# First_schematic.net
KiCad netlist of a schematic drawn in EAGLE
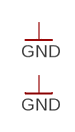
[diagram p0: schematic, sheet 1, part 1 of 2]
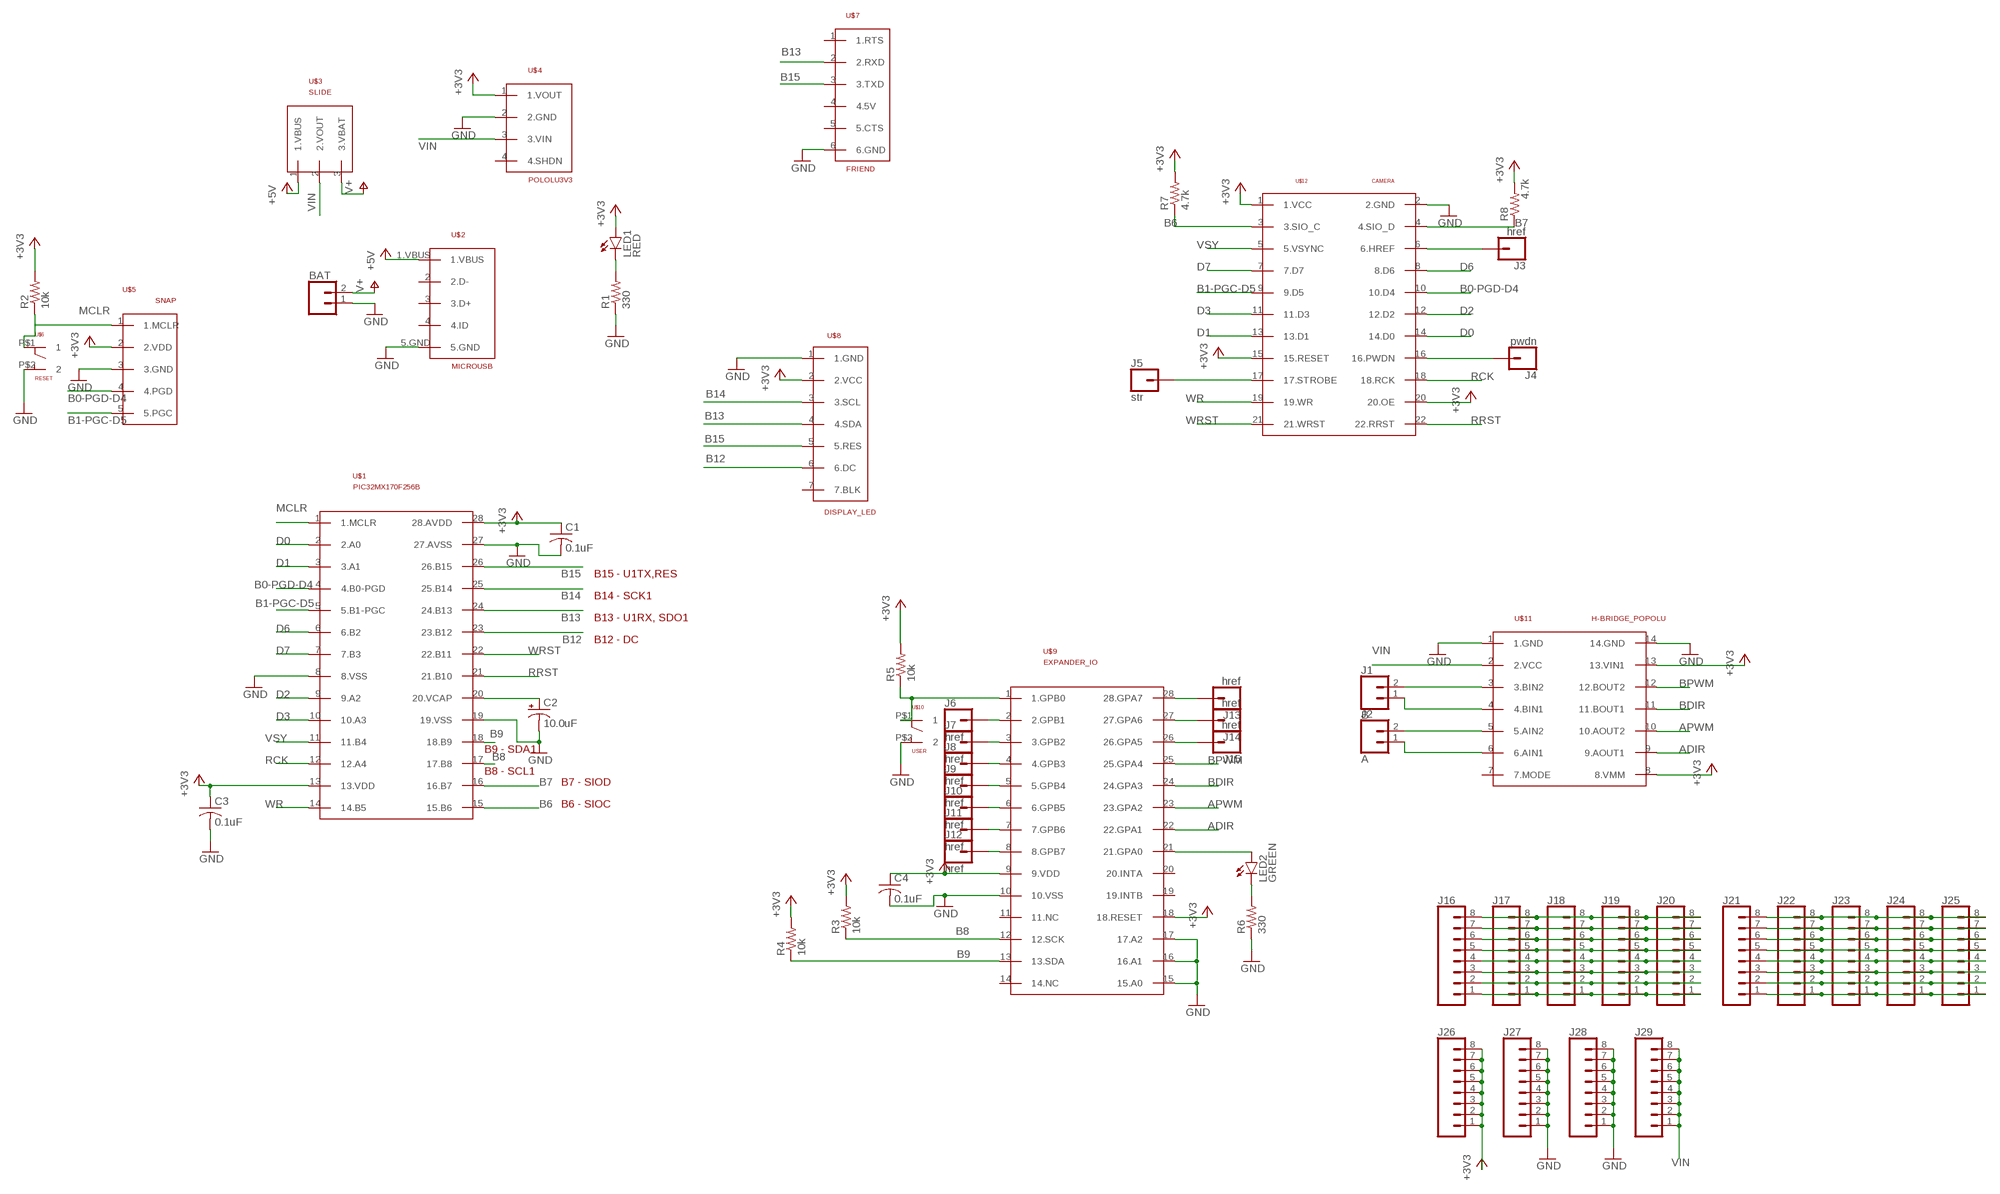
[diagram p1: schematic, sheet 1, part 2 of 2]

(export (version "E")
  (design (tool "Eeschema 10.0.6"))
  (components
    (comp (ref "BAT")
      (value "CONN_02")
      (footprint "eagle-import:1X02")
      (libsource (lib "eagle-import") (part "CONN_02"))
    )
    (comp (ref "C1")
      (value "0.1uF")
      (footprint "eagle-import:C025-030X050")
      (libsource (lib "eagle-import") (part "C-US025-030X050"))
    )
    (comp (ref "C2")
      (value "10.0uF")
      (footprint "eagle-import:B45181B")
      (libsource (lib "eagle-import") (part "CPOL-USB45181B"))
    )
    (comp (ref "C3")
      (value "0.1uF")
      (footprint "eagle-import:C025-030X050")
      (libsource (lib "eagle-import") (part "C-US025-030X050"))
    )
    (comp (ref "C4")
      (value "0.1uF")
      (footprint "eagle-import:C025-030X050")
      (libsource (lib "eagle-import") (part "C-US025-030X050"))
    )
    (comp (ref "J1")
      (value "B")
      (footprint "eagle-import:1X02")
      (libsource (lib "eagle-import") (part "CONN_02"))
    )
    (comp (ref "J2")
      (value "A")
      (footprint "eagle-import:1X02")
      (libsource (lib "eagle-import") (part "CONN_02"))
    )
    (comp (ref "J3")
      (value "href")
      (footprint "eagle-import:1X01")
      (libsource (lib "eagle-import") (part "CONN_01"))
    )
    (comp (ref "J4")
      (value "pwdn")
      (footprint "eagle-import:1X01")
      (libsource (lib "eagle-import") (part "CONN_01"))
    )
    (comp (ref "J5")
      (value "str")
      (footprint "eagle-import:1X01")
      (libsource (lib "eagle-import") (part "CONN_01"))
    )
    (comp (ref "J6")
      (value "href")
      (footprint "eagle-import:1X01")
      (libsource (lib "eagle-import") (part "CONN_01"))
    )
    (comp (ref "J7")
      (value "href")
      (footprint "eagle-import:1X01")
      (libsource (lib "eagle-import") (part "CONN_01"))
    )
    (comp (ref "J8")
      (value "href")
      (footprint "eagle-import:1X01")
      (libsource (lib "eagle-import") (part "CONN_01"))
    )
    (comp (ref "J9")
      (value "href")
      (footprint "eagle-import:1X01")
      (libsource (lib "eagle-import") (part "CONN_01"))
    )
    (comp (ref "J10")
      (value "href")
      (footprint "eagle-import:1X01")
      (libsource (lib "eagle-import") (part "CONN_01"))
    )
    (comp (ref "J11")
      (value "href")
      (footprint "eagle-import:1X01")
      (libsource (lib "eagle-import") (part "CONN_01"))
    )
    (comp (ref "J12")
      (value "href")
      (footprint "eagle-import:1X01")
      (libsource (lib "eagle-import") (part "CONN_01"))
    )
    (comp (ref "J13")
      (value "href")
      (footprint "eagle-import:1X01")
      (libsource (lib "eagle-import") (part "CONN_01"))
    )
    (comp (ref "J14")
      (value "href")
      (footprint "eagle-import:1X01")
      (libsource (lib "eagle-import") (part "CONN_01"))
    )
    (comp (ref "J15")
      (value "href")
      (footprint "eagle-import:1X01")
      (libsource (lib "eagle-import") (part "CONN_01"))
    )
    (comp (ref "J16")
      (value "CONN_08\"")
      (footprint "eagle-import:1X08")
      (libsource (lib "eagle-import") (part "CONN_08{dblquote}"))
    )
    (comp (ref "J17")
      (value "CONN_08\"")
      (footprint "eagle-import:1X08")
      (libsource (lib "eagle-import") (part "CONN_08{dblquote}"))
    )
    (comp (ref "J18")
      (value "CONN_08\"")
      (footprint "eagle-import:1X08")
      (libsource (lib "eagle-import") (part "CONN_08{dblquote}"))
    )
    (comp (ref "J19")
      (value "CONN_08\"")
      (footprint "eagle-import:1X08")
      (libsource (lib "eagle-import") (part "CONN_08{dblquote}"))
    )
    (comp (ref "J20")
      (value "CONN_08\"")
      (footprint "eagle-import:1X08")
      (libsource (lib "eagle-import") (part "CONN_08{dblquote}"))
    )
    (comp (ref "J21")
      (value "CONN_08\"")
      (footprint "eagle-import:1X08")
      (libsource (lib "eagle-import") (part "CONN_08{dblquote}"))
    )
    (comp (ref "J22")
      (value "CONN_08\"")
      (footprint "eagle-import:1X08")
      (libsource (lib "eagle-import") (part "CONN_08{dblquote}"))
    )
    (comp (ref "J23")
      (value "CONN_08\"")
      (footprint "eagle-import:1X08")
      (libsource (lib "eagle-import") (part "CONN_08{dblquote}"))
    )
    (comp (ref "J24")
      (value "CONN_08\"")
      (footprint "eagle-import:1X08")
      (libsource (lib "eagle-import") (part "CONN_08{dblquote}"))
    )
    (comp (ref "J25")
      (value "CONN_08\"")
      (footprint "eagle-import:1X08")
      (libsource (lib "eagle-import") (part "CONN_08{dblquote}"))
    )
    (comp (ref "J26")
      (value "CONN_08\"")
      (footprint "eagle-import:1X08")
      (libsource (lib "eagle-import") (part "CONN_08{dblquote}"))
    )
    (comp (ref "J27")
      (value "CONN_08\"")
      (footprint "eagle-import:1X08")
      (libsource (lib "eagle-import") (part "CONN_08{dblquote}"))
    )
    (comp (ref "J28")
      (value "CONN_08\"")
      (footprint "eagle-import:1X08")
      (libsource (lib "eagle-import") (part "CONN_08{dblquote}"))
    )
    (comp (ref "J29")
      (value "CONN_08\"")
      (footprint "eagle-import:1X08")
      (libsource (lib "eagle-import") (part "CONN_08{dblquote}"))
    )
    (comp (ref "LED1")
      (value "RED")
      (footprint "eagle-import:LED3MM")
      (libsource (lib "eagle-import") (part "LED3MM"))
    )
    (comp (ref "LED2")
      (value "GREEN")
      (footprint "eagle-import:LED3MM")
      (libsource (lib "eagle-import") (part "LED3MM"))
    )
    (comp (ref "R1")
      (value "330")
      (footprint "eagle-import:0207_10")
      (libsource (lib "eagle-import") (part "R-US_0207/10"))
    )
    (comp (ref "R2")
      (value "10k")
      (footprint "eagle-import:0207_10")
      (libsource (lib "eagle-import") (part "R-US_0207/10"))
    )
    (comp (ref "R3")
      (value "10k")
      (footprint "eagle-import:0207_10")
      (libsource (lib "eagle-import") (part "R-US_0207/10"))
    )
    (comp (ref "R4")
      (value "10k")
      (footprint "eagle-import:0207_10")
      (libsource (lib "eagle-import") (part "R-US_0207/10"))
    )
    (comp (ref "R5")
      (value "10k")
      (footprint "eagle-import:0207_10")
      (libsource (lib "eagle-import") (part "R-US_0207/10"))
    )
    (comp (ref "R6")
      (value "330")
      (footprint "eagle-import:0207_10")
      (libsource (lib "eagle-import") (part "R-US_0207/10"))
    )
    (comp (ref "R7")
      (value "4.7k")
      (footprint "eagle-import:0207_10")
      (libsource (lib "eagle-import") (part "R-US_0207/10"))
    )
    (comp (ref "R8")
      (value "4.7k")
      (footprint "eagle-import:0207_10")
      (libsource (lib "eagle-import") (part "R-US_0207/10"))
    )
    (comp (ref "U$1")
      (value "PIC32MX170F256B")
      (footprint "eagle-import:DIL28-3")
      (libsource (lib "eagle-import") (part "PIC32MX170F256B"))
    )
    (comp (ref "U$2")
      (value "MICROUSB")
      (footprint "eagle-import:MICROUSB")
      (libsource (lib "eagle-import") (part "MICROUSB"))
    )
    (comp (ref "U$3")
      (value "SLIDE")
      (footprint "eagle-import:SLIDE")
      (libsource (lib "eagle-import") (part "SLIDE"))
    )
    (comp (ref "U$4")
      (value "POLOLU3V3")
      (footprint "eagle-import:POLOLU3V3")
      (libsource (lib "eagle-import") (part "POLOLU3V3"))
    )
    (comp (ref "U$5")
      (value "SNAP")
      (footprint "eagle-import:1X05")
      (libsource (lib "eagle-import") (part "SNAP"))
    )
    (comp (ref "U$6")
      (value "RESET")
      (footprint "eagle-import:PUSH")
      (libsource (lib "eagle-import") (part "PUSH"))
    )
    (comp (ref "U$7")
      (value "FRIEND")
      (footprint "eagle-import:FRIEND")
      (libsource (lib "eagle-import") (part "FRIEND"))
    )
    (comp (ref "U$8")
      (value "DISPLAY_LED")
      (footprint "eagle-import:DISPLAY_LED")
      (libsource (lib "eagle-import") (part "DISPLAY_LED"))
    )
    (comp (ref "U$9")
      (value "EXPANDER_IO")
      (footprint "eagle-import:DIL28-3")
      (libsource (lib "eagle-import") (part "EXPANDER_IO"))
    )
    (comp (ref "U$10")
      (value "USER")
      (footprint "eagle-import:PUSH")
      (libsource (lib "eagle-import") (part "PUSH"))
    )
    (comp (ref "U$11")
      (value "H-BRIDGE_POPOLU")
      (footprint "eagle-import:H-BRIDGE_POLOLU")
      (libsource (lib "eagle-import") (part "H-BRIDGE_POPOLU"))
    )
    (comp (ref "U$12")
      (value "CAMERA")
      (footprint "eagle-import:CAMERA_REAL_SIZE")
      (libsource (lib "eagle-import") (part "CAMERA"))
    )
  )
  (nets
    (net (code "1") (name "+3V3") (class "Default")
      (node (ref "C1") (pin "1") (pinfunction "1_1") (pintype "passive"))
      (node (ref "C3") (pin "1") (pinfunction "1_1") (pintype "passive"))
      (node (ref "C4") (pin "1") (pinfunction "1_1") (pintype "passive"))
      (node (ref "J26") (pin "1") (pinfunction "1_1") (pintype "passive"))
      (node (ref "J26") (pin "2") (pinfunction "2_2") (pintype "passive"))
      (node (ref "J26") (pin "3") (pinfunction "3_3") (pintype "passive"))
      (node (ref "J26") (pin "4") (pinfunction "4_4") (pintype "passive"))
      (node (ref "J26") (pin "5") (pinfunction "5_5") (pintype "passive"))
      (node (ref "J26") (pin "6") (pinfunction "6_6") (pintype "passive"))
      (node (ref "J26") (pin "7") (pinfunction "7_7") (pintype "passive"))
      (node (ref "J26") (pin "8") (pinfunction "8_8") (pintype "passive"))
      (node (ref "LED1") (pin "A") (pinfunction "A_A") (pintype "passive"))
      (node (ref "R2") (pin "2") (pinfunction "2_2") (pintype "passive"))
      (node (ref "R3") (pin "2") (pinfunction "2_2") (pintype "passive"))
      (node (ref "R4") (pin "2") (pinfunction "2_2") (pintype "passive"))
      (node (ref "R5") (pin "2") (pinfunction "2_2") (pintype "passive"))
      (node (ref "R7") (pin "2") (pinfunction "2_2") (pintype "passive"))
      (node (ref "R8") (pin "2") (pinfunction "2_2") (pintype "passive"))
      (node (ref "U$1") (pin "13") (pinfunction "13.VDD_13") (pintype "bidirectional"))
      (node (ref "U$1") (pin "28") (pinfunction "28.AVDD_28") (pintype "bidirectional"))
      (node (ref "U$11") (pin "13") (pinfunction "13.VIN1_13") (pintype "bidirectional"))
      (node (ref "U$11") (pin "8") (pinfunction "8.VMM_8") (pintype "bidirectional"))
      (node (ref "U$12") (pin "1") (pinfunction "1.VCC_1") (pintype "bidirectional"))
      (node (ref "U$12") (pin "15") (pinfunction "15.RESET_15") (pintype "bidirectional"))
      (node (ref "U$12") (pin "20") (pinfunction "20.OE_20") (pintype "bidirectional"))
      (node (ref "U$4") (pin "1") (pinfunction "1.VOUT_1") (pintype "bidirectional"))
      (node (ref "U$5") (pin "2") (pinfunction "2.VDD_2") (pintype "bidirectional"))
      (node (ref "U$8") (pin "2") (pinfunction "2.VCC_2") (pintype "bidirectional"))
      (node (ref "U$9") (pin "18") (pinfunction "18.RESET_18") (pintype "bidirectional"))
      (node (ref "U$9") (pin "9") (pinfunction "9.VDD_9") (pintype "bidirectional"))
    )
    (net (code "2") (name "+5V") (class "Default")
      (node (ref "U$2") (pin "1.VBUS") (pinfunction "1.VBUS_1.VBUS") (pintype "bidirectional"))
      (node (ref "U$3") (pin "1") (pinfunction "1.VBUS_1") (pintype "bidirectional"))
    )
    (net (code "3") (name "/ADIR") (class "Default")
      (node (ref "U$11") (pin "9") (pinfunction "9.AOUT1_9") (pintype "bidirectional"))
      (node (ref "U$9") (pin "22") (pinfunction "22.GPA1_22") (pintype "bidirectional"))
    )
    (net (code "4") (name "/APWM") (class "Default")
      (node (ref "U$11") (pin "10") (pinfunction "10.AOUT2_10") (pintype "bidirectional"))
      (node (ref "U$9") (pin "23") (pinfunction "23.GPA2_23") (pintype "bidirectional"))
    )
    (net (code "5") (name "/B0-PGD-D4") (class "Default")
      (node (ref "U$1") (pin "4") (pinfunction "4.B0-PGD_4") (pintype "bidirectional"))
      (node (ref "U$12") (pin "10") (pinfunction "10.D4_10") (pintype "bidirectional"))
      (node (ref "U$5") (pin "4") (pinfunction "4.PGD_4") (pintype "bidirectional"))
    )
    (net (code "6") (name "/B1-PGC-D5") (class "Default")
      (node (ref "U$1") (pin "5") (pinfunction "5.B1-PGC_5") (pintype "bidirectional"))
      (node (ref "U$12") (pin "9") (pinfunction "9.D5_9") (pintype "bidirectional"))
      (node (ref "U$5") (pin "5") (pinfunction "5.PGC_5") (pintype "bidirectional"))
    )
    (net (code "7") (name "/B6") (class "Default")
      (node (ref "R7") (pin "1") (pinfunction "1_1") (pintype "passive"))
      (node (ref "U$1") (pin "15") (pinfunction "15.B6_15") (pintype "bidirectional"))
      (node (ref "U$12") (pin "3") (pinfunction "3.SIO_C_3") (pintype "bidirectional"))
    )
    (net (code "8") (name "/B7") (class "Default")
      (node (ref "R8") (pin "1") (pinfunction "1_1") (pintype "passive"))
      (node (ref "U$1") (pin "16") (pinfunction "16.B7_16") (pintype "bidirectional"))
      (node (ref "U$12") (pin "4") (pinfunction "4.SIO_D_4") (pintype "bidirectional"))
    )
    (net (code "9") (name "/B8") (class "Default")
      (node (ref "R3") (pin "1") (pinfunction "1_1") (pintype "passive"))
      (node (ref "U$1") (pin "17") (pinfunction "17.B8_17") (pintype "bidirectional"))
      (node (ref "U$9") (pin "12") (pinfunction "12.SCK_12") (pintype "bidirectional"))
    )
    (net (code "10") (name "/B9") (class "Default")
      (node (ref "R4") (pin "1") (pinfunction "1_1") (pintype "passive"))
      (node (ref "U$1") (pin "18") (pinfunction "18.B9_18") (pintype "bidirectional"))
      (node (ref "U$9") (pin "13") (pinfunction "13.SDA_13") (pintype "bidirectional"))
    )
    (net (code "11") (name "/B12") (class "Default")
      (node (ref "U$1") (pin "23") (pinfunction "23.B12_23") (pintype "bidirectional"))
      (node (ref "U$8") (pin "6") (pinfunction "6.DC_6") (pintype "bidirectional"))
    )
    (net (code "12") (name "/B13") (class "Default")
      (node (ref "U$1") (pin "24") (pinfunction "24.B13_24") (pintype "bidirectional"))
      (node (ref "U$7") (pin "2") (pinfunction "2.RXD_2") (pintype "bidirectional"))
      (node (ref "U$8") (pin "4") (pinfunction "4.SDA_4") (pintype "bidirectional"))
    )
    (net (code "13") (name "/B14") (class "Default")
      (node (ref "U$1") (pin "25") (pinfunction "25.B14_25") (pintype "bidirectional"))
      (node (ref "U$8") (pin "3") (pinfunction "3.SCL_3") (pintype "bidirectional"))
    )
    (net (code "14") (name "/B15") (class "Default")
      (node (ref "U$1") (pin "26") (pinfunction "26.B15_26") (pintype "bidirectional"))
      (node (ref "U$7") (pin "3") (pinfunction "3.TXD_3") (pintype "bidirectional"))
      (node (ref "U$8") (pin "5") (pinfunction "5.RES_5") (pintype "bidirectional"))
    )
    (net (code "15") (name "/BDIR") (class "Default")
      (node (ref "U$11") (pin "11") (pinfunction "11.BOUT1_11") (pintype "bidirectional"))
      (node (ref "U$9") (pin "24") (pinfunction "24.GPA3_24") (pintype "bidirectional"))
    )
    (net (code "16") (name "/BPWM") (class "Default")
      (node (ref "U$11") (pin "12") (pinfunction "12.BOUT2_12") (pintype "bidirectional"))
      (node (ref "U$9") (pin "25") (pinfunction "25.GPA4_25") (pintype "bidirectional"))
    )
    (net (code "17") (name "/D0") (class "Default")
      (node (ref "U$1") (pin "2") (pinfunction "2.A0_2") (pintype "bidirectional"))
      (node (ref "U$12") (pin "14") (pinfunction "14.D0_14") (pintype "bidirectional"))
    )
    (net (code "18") (name "/D1") (class "Default")
      (node (ref "U$1") (pin "3") (pinfunction "3.A1_3") (pintype "bidirectional"))
      (node (ref "U$12") (pin "13") (pinfunction "13.D1_13") (pintype "bidirectional"))
    )
    (net (code "19") (name "/D2") (class "Default")
      (node (ref "U$1") (pin "9") (pinfunction "9.A2_9") (pintype "bidirectional"))
      (node (ref "U$12") (pin "12") (pinfunction "12.D2_12") (pintype "bidirectional"))
    )
    (net (code "20") (name "/D3") (class "Default")
      (node (ref "U$1") (pin "10") (pinfunction "10.A3_10") (pintype "bidirectional"))
      (node (ref "U$12") (pin "11") (pinfunction "11.D3_11") (pintype "bidirectional"))
    )
    (net (code "21") (name "/D6") (class "Default")
      (node (ref "U$1") (pin "6") (pinfunction "6.B2_6") (pintype "bidirectional"))
      (node (ref "U$12") (pin "8") (pinfunction "8.D6_8") (pintype "bidirectional"))
    )
    (net (code "22") (name "/D7") (class "Default")
      (node (ref "U$1") (pin "7") (pinfunction "7.B3_7") (pintype "bidirectional"))
      (node (ref "U$12") (pin "7") (pinfunction "7.D7_7") (pintype "bidirectional"))
    )
    (net (code "23") (name "/MCLR") (class "Default")
      (node (ref "U$1") (pin "1") (pinfunction "1.MCLR_1") (pintype "bidirectional"))
      (node (ref "U$5") (pin "1") (pinfunction "1.MCLR_1") (pintype "bidirectional"))
    )
    (net (code "24") (name "/RCK") (class "Default")
      (node (ref "U$1") (pin "12") (pinfunction "12.A4_12") (pintype "bidirectional"))
      (node (ref "U$12") (pin "18") (pinfunction "18.RCK_18") (pintype "bidirectional"))
    )
    (net (code "25") (name "/RRST") (class "Default")
      (node (ref "U$1") (pin "21") (pinfunction "21.B10_21") (pintype "bidirectional"))
      (node (ref "U$12") (pin "22") (pinfunction "22.RRST_22") (pintype "bidirectional"))
    )
    (net (code "26") (name "/VIN") (class "Default")
      (node (ref "J29") (pin "1") (pinfunction "1_1") (pintype "passive"))
      (node (ref "J29") (pin "2") (pinfunction "2_2") (pintype "passive"))
      (node (ref "J29") (pin "3") (pinfunction "3_3") (pintype "passive"))
      (node (ref "J29") (pin "4") (pinfunction "4_4") (pintype "passive"))
      (node (ref "J29") (pin "5") (pinfunction "5_5") (pintype "passive"))
      (node (ref "J29") (pin "6") (pinfunction "6_6") (pintype "passive"))
      (node (ref "J29") (pin "7") (pinfunction "7_7") (pintype "passive"))
      (node (ref "J29") (pin "8") (pinfunction "8_8") (pintype "passive"))
      (node (ref "U$11") (pin "2") (pinfunction "2.VCC_2") (pintype "bidirectional"))
      (node (ref "U$3") (pin "2") (pinfunction "2.VOUT_2") (pintype "bidirectional"))
      (node (ref "U$4") (pin "3") (pinfunction "3.VIN_3") (pintype "bidirectional"))
    )
    (net (code "27") (name "/VSY") (class "Default")
      (node (ref "U$1") (pin "11") (pinfunction "11.B4_11") (pintype "bidirectional"))
      (node (ref "U$12") (pin "5") (pinfunction "5.VSYNC_5") (pintype "bidirectional"))
    )
    (net (code "28") (name "/WR") (class "Default")
      (node (ref "U$1") (pin "14") (pinfunction "14.B5_14") (pintype "bidirectional"))
      (node (ref "U$12") (pin "19") (pinfunction "19.WR_19") (pintype "bidirectional"))
    )
    (net (code "29") (name "/WRST") (class "Default")
      (node (ref "U$1") (pin "22") (pinfunction "22.B11_22") (pintype "bidirectional"))
      (node (ref "U$12") (pin "21") (pinfunction "21.WRST_21") (pintype "bidirectional"))
    )
    (net (code "30") (name "GND") (class "Default")
      (node (ref "BAT") (pin "1") (pinfunction "1_1") (pintype "passive"))
      (node (ref "C1") (pin "2") (pinfunction "2_2") (pintype "passive"))
      (node (ref "C2") (pin "-") (pinfunction "-_-") (pintype "passive"))
      (node (ref "C3") (pin "2") (pinfunction "2_2") (pintype "passive"))
      (node (ref "C4") (pin "2") (pinfunction "2_2") (pintype "passive"))
      (node (ref "J27") (pin "1") (pinfunction "1_1") (pintype "passive"))
      (node (ref "J27") (pin "2") (pinfunction "2_2") (pintype "passive"))
      (node (ref "J27") (pin "3") (pinfunction "3_3") (pintype "passive"))
      (node (ref "J27") (pin "4") (pinfunction "4_4") (pintype "passive"))
      (node (ref "J27") (pin "5") (pinfunction "5_5") (pintype "passive"))
      (node (ref "J27") (pin "6") (pinfunction "6_6") (pintype "passive"))
      (node (ref "J27") (pin "7") (pinfunction "7_7") (pintype "passive"))
      (node (ref "J27") (pin "8") (pinfunction "8_8") (pintype "passive"))
      (node (ref "J28") (pin "1") (pinfunction "1_1") (pintype "passive"))
      (node (ref "J28") (pin "2") (pinfunction "2_2") (pintype "passive"))
      (node (ref "J28") (pin "3") (pinfunction "3_3") (pintype "passive"))
      (node (ref "J28") (pin "4") (pinfunction "4_4") (pintype "passive"))
      (node (ref "J28") (pin "5") (pinfunction "5_5") (pintype "passive"))
      (node (ref "J28") (pin "6") (pinfunction "6_6") (pintype "passive"))
      (node (ref "J28") (pin "7") (pinfunction "7_7") (pintype "passive"))
      (node (ref "J28") (pin "8") (pinfunction "8_8") (pintype "passive"))
      (node (ref "R1") (pin "1") (pinfunction "1_1") (pintype "passive"))
      (node (ref "R6") (pin "1") (pinfunction "1_1") (pintype "passive"))
      (node (ref "U$1") (pin "19") (pinfunction "19.VSS_19") (pintype "bidirectional"))
      (node (ref "U$1") (pin "27") (pinfunction "27.AVSS_27") (pintype "bidirectional"))
      (node (ref "U$1") (pin "8") (pinfunction "8.VSS_8") (pintype "bidirectional"))
      (node (ref "U$10") (pin "P$2") (pinfunction "2_P$2") (pintype "bidirectional"))
      (node (ref "U$11") (pin "1") (pinfunction "1.GND_1") (pintype "bidirectional"))
      (node (ref "U$11") (pin "14") (pinfunction "14.GND_14") (pintype "bidirectional"))
      (node (ref "U$12") (pin "2") (pinfunction "2.GND_2") (pintype "bidirectional"))
      (node (ref "U$2") (pin "5.GND") (pinfunction "5.GND_5.GND") (pintype "bidirectional"))
      (node (ref "U$4") (pin "2") (pinfunction "2.GND_2") (pintype "bidirectional"))
      (node (ref "U$5") (pin "3") (pinfunction "3.GND_3") (pintype "bidirectional"))
      (node (ref "U$6") (pin "P$2") (pinfunction "2_P$2") (pintype "bidirectional"))
      (node (ref "U$7") (pin "6") (pinfunction "6.GND_6") (pintype "bidirectional"))
      (node (ref "U$8") (pin "1") (pinfunction "1.GND_1") (pintype "bidirectional"))
      (node (ref "U$9") (pin "10") (pinfunction "10.VSS_10") (pintype "bidirectional"))
      (node (ref "U$9") (pin "15") (pinfunction "15.A0_15") (pintype "bidirectional"))
      (node (ref "U$9") (pin "16") (pinfunction "16.A1_16") (pintype "bidirectional"))
      (node (ref "U$9") (pin "17") (pinfunction "17.A2_17") (pintype "bidirectional"))
    )
    (net (code "31") (name "Net-(J16-Pad1)") (class "Default")
      (node (ref "J16") (pin "1") (pinfunction "1_1") (pintype "passive"))
      (node (ref "J17") (pin "1") (pinfunction "1_1") (pintype "passive"))
      (node (ref "J18") (pin "1") (pinfunction "1_1") (pintype "passive"))
      (node (ref "J19") (pin "1") (pinfunction "1_1") (pintype "passive"))
      (node (ref "J20") (pin "1") (pinfunction "1_1") (pintype "passive"))
    )
    (net (code "32") (name "Net-(J16-Pad2)") (class "Default")
      (node (ref "J16") (pin "2") (pinfunction "2_2") (pintype "passive"))
      (node (ref "J17") (pin "2") (pinfunction "2_2") (pintype "passive"))
      (node (ref "J18") (pin "2") (pinfunction "2_2") (pintype "passive"))
      (node (ref "J19") (pin "2") (pinfunction "2_2") (pintype "passive"))
      (node (ref "J20") (pin "2") (pinfunction "2_2") (pintype "passive"))
    )
    (net (code "33") (name "Net-(J16-Pad3)") (class "Default")
      (node (ref "J16") (pin "3") (pinfunction "3_3") (pintype "passive"))
      (node (ref "J17") (pin "3") (pinfunction "3_3") (pintype "passive"))
      (node (ref "J18") (pin "3") (pinfunction "3_3") (pintype "passive"))
      (node (ref "J19") (pin "3") (pinfunction "3_3") (pintype "passive"))
      (node (ref "J20") (pin "3") (pinfunction "3_3") (pintype "passive"))
    )
    (net (code "34") (name "Net-(J16-Pad4)") (class "Default")
      (node (ref "J16") (pin "4") (pinfunction "4_4") (pintype "passive"))
      (node (ref "J17") (pin "4") (pinfunction "4_4") (pintype "passive"))
      (node (ref "J18") (pin "4") (pinfunction "4_4") (pintype "passive"))
      (node (ref "J19") (pin "4") (pinfunction "4_4") (pintype "passive"))
      (node (ref "J20") (pin "4") (pinfunction "4_4") (pintype "passive"))
    )
    (net (code "35") (name "Net-(J16-Pad5)") (class "Default")
      (node (ref "J16") (pin "5") (pinfunction "5_5") (pintype "passive"))
      (node (ref "J17") (pin "5") (pinfunction "5_5") (pintype "passive"))
      (node (ref "J18") (pin "5") (pinfunction "5_5") (pintype "passive"))
      (node (ref "J19") (pin "5") (pinfunction "5_5") (pintype "passive"))
      (node (ref "J20") (pin "5") (pinfunction "5_5") (pintype "passive"))
    )
    (net (code "36") (name "Net-(J16-Pad6)") (class "Default")
      (node (ref "J16") (pin "6") (pinfunction "6_6") (pintype "passive"))
      (node (ref "J17") (pin "6") (pinfunction "6_6") (pintype "passive"))
      (node (ref "J18") (pin "6") (pinfunction "6_6") (pintype "passive"))
      (node (ref "J19") (pin "6") (pinfunction "6_6") (pintype "passive"))
      (node (ref "J20") (pin "6") (pinfunction "6_6") (pintype "passive"))
    )
    (net (code "37") (name "Net-(J16-Pad7)") (class "Default")
      (node (ref "J16") (pin "7") (pinfunction "7_7") (pintype "passive"))
      (node (ref "J17") (pin "7") (pinfunction "7_7") (pintype "passive"))
      (node (ref "J18") (pin "7") (pinfunction "7_7") (pintype "passive"))
      (node (ref "J19") (pin "7") (pinfunction "7_7") (pintype "passive"))
      (node (ref "J20") (pin "7") (pinfunction "7_7") (pintype "passive"))
    )
    (net (code "38") (name "Net-(J16-Pad8)") (class "Default")
      (node (ref "J16") (pin "8") (pinfunction "8_8") (pintype "passive"))
      (node (ref "J17") (pin "8") (pinfunction "8_8") (pintype "passive"))
      (node (ref "J18") (pin "8") (pinfunction "8_8") (pintype "passive"))
      (node (ref "J19") (pin "8") (pinfunction "8_8") (pintype "passive"))
      (node (ref "J20") (pin "8") (pinfunction "8_8") (pintype "passive"))
    )
    (net (code "39") (name "Net-(J21-Pad1)") (class "Default")
      (node (ref "J21") (pin "1") (pinfunction "1_1") (pintype "passive"))
      (node (ref "J22") (pin "1") (pinfunction "1_1") (pintype "passive"))
      (node (ref "J23") (pin "1") (pinfunction "1_1") (pintype "passive"))
      (node (ref "J24") (pin "1") (pinfunction "1_1") (pintype "passive"))
      (node (ref "J25") (pin "1") (pinfunction "1_1") (pintype "passive"))
    )
    (net (code "40") (name "Net-(J21-Pad2)") (class "Default")
      (node (ref "J21") (pin "2") (pinfunction "2_2") (pintype "passive"))
      (node (ref "J22") (pin "2") (pinfunction "2_2") (pintype "passive"))
      (node (ref "J23") (pin "2") (pinfunction "2_2") (pintype "passive"))
      (node (ref "J24") (pin "2") (pinfunction "2_2") (pintype "passive"))
      (node (ref "J25") (pin "2") (pinfunction "2_2") (pintype "passive"))
    )
    (net (code "41") (name "Net-(J21-Pad3)") (class "Default")
      (node (ref "J21") (pin "3") (pinfunction "3_3") (pintype "passive"))
      (node (ref "J22") (pin "3") (pinfunction "3_3") (pintype "passive"))
      (node (ref "J23") (pin "3") (pinfunction "3_3") (pintype "passive"))
      (node (ref "J24") (pin "3") (pinfunction "3_3") (pintype "passive"))
      (node (ref "J25") (pin "3") (pinfunction "3_3") (pintype "passive"))
    )
    (net (code "42") (name "Net-(J21-Pad4)") (class "Default")
      (node (ref "J21") (pin "4") (pinfunction "4_4") (pintype "passive"))
      (node (ref "J22") (pin "4") (pinfunction "4_4") (pintype "passive"))
      (node (ref "J23") (pin "4") (pinfunction "4_4") (pintype "passive"))
      (node (ref "J24") (pin "4") (pinfunction "4_4") (pintype "passive"))
      (node (ref "J25") (pin "4") (pinfunction "4_4") (pintype "passive"))
    )
    (net (code "43") (name "Net-(J21-Pad5)") (class "Default")
      (node (ref "J21") (pin "5") (pinfunction "5_5") (pintype "passive"))
      (node (ref "J22") (pin "5") (pinfunction "5_5") (pintype "passive"))
      (node (ref "J23") (pin "5") (pinfunction "5_5") (pintype "passive"))
      (node (ref "J24") (pin "5") (pinfunction "5_5") (pintype "passive"))
      (node (ref "J25") (pin "5") (pinfunction "5_5") (pintype "passive"))
    )
    (net (code "44") (name "Net-(J21-Pad6)") (class "Default")
      (node (ref "J21") (pin "6") (pinfunction "6_6") (pintype "passive"))
      (node (ref "J22") (pin "6") (pinfunction "6_6") (pintype "passive"))
      (node (ref "J23") (pin "6") (pinfunction "6_6") (pintype "passive"))
      (node (ref "J24") (pin "6") (pinfunction "6_6") (pintype "passive"))
      (node (ref "J25") (pin "6") (pinfunction "6_6") (pintype "passive"))
    )
    (net (code "45") (name "Net-(J21-Pad7)") (class "Default")
      (node (ref "J21") (pin "7") (pinfunction "7_7") (pintype "passive"))
      (node (ref "J22") (pin "7") (pinfunction "7_7") (pintype "passive"))
      (node (ref "J23") (pin "7") (pinfunction "7_7") (pintype "passive"))
      (node (ref "J24") (pin "7") (pinfunction "7_7") (pintype "passive"))
      (node (ref "J25") (pin "7") (pinfunction "7_7") (pintype "passive"))
    )
    (net (code "46") (name "Net-(J21-Pad8)") (class "Default")
      (node (ref "J21") (pin "8") (pinfunction "8_8") (pintype "passive"))
      (node (ref "J22") (pin "8") (pinfunction "8_8") (pintype "passive"))
      (node (ref "J23") (pin "8") (pinfunction "8_8") (pintype "passive"))
      (node (ref "J24") (pin "8") (pinfunction "8_8") (pintype "passive"))
      (node (ref "J25") (pin "8") (pinfunction "8_8") (pintype "passive"))
    )
    (net (code "47") (name "Net-(LED1-C)") (class "Default")
      (node (ref "LED1") (pin "K") (pinfunction "C_K") (pintype "passive"))
      (node (ref "R1") (pin "2") (pinfunction "2_2") (pintype "passive"))
    )
    (net (code "48") (name "Net-(LED2-C)") (class "Default")
      (node (ref "LED2") (pin "K") (pinfunction "C_K") (pintype "passive"))
      (node (ref "R6") (pin "2") (pinfunction "2_2") (pintype "passive"))
    )
    (net (code "49") (name "Net-(U$1-20.VCAP)") (class "Default")
      (node (ref "C2") (pin "+") (pinfunction "+_+") (pintype "passive"))
      (node (ref "U$1") (pin "20") (pinfunction "20.VCAP_20") (pintype "bidirectional"))
    )
    (net (code "50") (name "Net-(U$6-1)") (class "Default")
      (node (ref "R2") (pin "1") (pinfunction "1_1") (pintype "passive"))
      (node (ref "U$6") (pin "P$1") (pinfunction "1_P$1") (pintype "bidirectional"))
    )
    (net (code "51") (name "Net-(U$9-2.GPB1)") (class "Default")
      (node (ref "J6") (pin "1") (pinfunction "1_1") (pintype "passive"))
      (node (ref "U$9") (pin "2") (pinfunction "2.GPB1_2") (pintype "bidirectional"))
    )
    (net (code "52") (name "Net-(U$9-3.GPB2)") (class "Default")
      (node (ref "J7") (pin "1") (pinfunction "1_1") (pintype "passive"))
      (node (ref "U$9") (pin "3") (pinfunction "3.GPB2_3") (pintype "bidirectional"))
    )
    (net (code "53") (name "Net-(U$9-4.GPB3)") (class "Default")
      (node (ref "J8") (pin "1") (pinfunction "1_1") (pintype "passive"))
      (node (ref "U$9") (pin "4") (pinfunction "4.GPB3_4") (pintype "bidirectional"))
    )
    (net (code "54") (name "Net-(U$9-5.GPB4)") (class "Default")
      (node (ref "J9") (pin "1") (pinfunction "1_1") (pintype "passive"))
      (node (ref "U$9") (pin "5") (pinfunction "5.GPB4_5") (pintype "bidirectional"))
    )
    (net (code "55") (name "Net-(U$9-6.GPB5)") (class "Default")
      (node (ref "J10") (pin "1") (pinfunction "1_1") (pintype "passive"))
      (node (ref "U$9") (pin "6") (pinfunction "6.GPB5_6") (pintype "bidirectional"))
    )
    (net (code "56") (name "Net-(U$9-7.GPB6)") (class "Default")
      (node (ref "J11") (pin "1") (pinfunction "1_1") (pintype "passive"))
      (node (ref "U$9") (pin "7") (pinfunction "7.GPB6_7") (pintype "bidirectional"))
    )
    (net (code "57") (name "Net-(U$9-8.GPB7)") (class "Default")
      (node (ref "J12") (pin "1") (pinfunction "1_1") (pintype "passive"))
      (node (ref "U$9") (pin "8") (pinfunction "8.GPB7_8") (pintype "bidirectional"))
    )
    (net (code "58") (name "Net-(U$9-21.GPA0)") (class "Default")
      (node (ref "LED2") (pin "A") (pinfunction "A_A") (pintype "passive"))
      (node (ref "U$9") (pin "21") (pinfunction "21.GPA0_21") (pintype "bidirectional"))
    )
    (net (code "59") (name "Net-(U$9-26.GPA5)") (class "Default")
      (node (ref "J15") (pin "1") (pinfunction "1_1") (pintype "passive"))
      (node (ref "U$9") (pin "26") (pinfunction "26.GPA5_26") (pintype "bidirectional"))
    )
    (net (code "60") (name "Net-(U$9-27.GPA6)") (class "Default")
      (node (ref "J14") (pin "1") (pinfunction "1_1") (pintype "passive"))
      (node (ref "U$9") (pin "27") (pinfunction "27.GPA6_27") (pintype "bidirectional"))
    )
    (net (code "61") (name "Net-(U$9-28.GPA7)") (class "Default")
      (node (ref "J13") (pin "1") (pinfunction "1_1") (pintype "passive"))
      (node (ref "U$9") (pin "28") (pinfunction "28.GPA7_28") (pintype "bidirectional"))
    )
    (net (code "62") (name "Net-(U$10-1)") (class "Default")
      (node (ref "R5") (pin "1") (pinfunction "1_1") (pintype "passive"))
      (node (ref "U$10") (pin "P$1") (pinfunction "1_P$1") (pintype "bidirectional"))
      (node (ref "U$9") (pin "1") (pinfunction "1.GPB0_1") (pintype "bidirectional"))
    )
    (net (code "63") (name "Net-(U$11-3.BIN2)") (class "Default")
      (node (ref "J1") (pin "2") (pinfunction "2_2") (pintype "passive"))
      (node (ref "U$11") (pin "3") (pinfunction "3.BIN2_3") (pintype "bidirectional"))
    )
    (net (code "64") (name "Net-(U$11-4.BIN1)") (class "Default")
      (node (ref "J1") (pin "1") (pinfunction "1_1") (pintype "passive"))
      (node (ref "U$11") (pin "4") (pinfunction "4.BIN1_4") (pintype "bidirectional"))
    )
    (net (code "65") (name "Net-(U$11-5.AIN2)") (class "Default")
      (node (ref "J2") (pin "2") (pinfunction "2_2") (pintype "passive"))
      (node (ref "U$11") (pin "5") (pinfunction "5.AIN2_5") (pintype "bidirectional"))
    )
    (net (code "66") (name "Net-(U$11-6.AIN1)") (class "Default")
      (node (ref "J2") (pin "1") (pinfunction "1_1") (pintype "passive"))
      (node (ref "U$11") (pin "6") (pinfunction "6.AIN1_6") (pintype "bidirectional"))
    )
    (net (code "67") (name "Net-(U$12-6.HREF)") (class "Default")
      (node (ref "J3") (pin "1") (pinfunction "1_1") (pintype "passive"))
      (node (ref "U$12") (pin "6") (pinfunction "6.HREF_6") (pintype "bidirectional"))
    )
    (net (code "68") (name "Net-(U$12-16.PWDN)") (class "Default")
      (node (ref "J4") (pin "1") (pinfunction "1_1") (pintype "passive"))
      (node (ref "U$12") (pin "16") (pinfunction "16.PWDN_16") (pintype "bidirectional"))
    )
    (net (code "69") (name "Net-(U$12-17.STROBE)") (class "Default")
      (node (ref "J5") (pin "1") (pinfunction "1_1") (pintype "passive"))
      (node (ref "U$12") (pin "17") (pinfunction "17.STROBE_17") (pintype "bidirectional"))
    )
    (net (code "70") (name "V+") (class "Default")
      (node (ref "BAT") (pin "2") (pinfunction "2_2") (pintype "passive"))
      (node (ref "U$3") (pin "3") (pinfunction "3.VBAT_3") (pintype "bidirectional"))
    )
    (net (code "71") (name "unconnected-(U$2-2.D--Pad2)") (class "Default")
      (node (ref "U$2") (pin "2") (pinfunction "2.D-_2") (pintype "bidirectional"))
    )
    (net (code "72") (name "unconnected-(U$2-3.D+-Pad3)") (class "Default")
      (node (ref "U$2") (pin "3") (pinfunction "3.D+_3") (pintype "bidirectional"))
    )
    (net (code "73") (name "unconnected-(U$2-4.ID-Pad4)") (class "Default")
      (node (ref "U$2") (pin "4") (pinfunction "4.ID_4") (pintype "bidirectional"))
    )
    (net (code "74") (name "unconnected-(U$4-4.SHDN-Pad4)") (class "Default")
      (node (ref "U$4") (pin "4") (pinfunction "4.SHDN_4") (pintype "bidirectional"))
    )
    (net (code "75") (name "unconnected-(U$7-1.RTS-Pad1)") (class "Default")
      (node (ref "U$7") (pin "1") (pinfunction "1.RTS_1") (pintype "bidirectional"))
    )
    (net (code "76") (name "unconnected-(U$7-4.5V-Pad4)") (class "Default")
      (node (ref "U$7") (pin "4") (pinfunction "4.5V_4") (pintype "bidirectional"))
    )
    (net (code "77") (name "unconnected-(U$7-5.CTS-Pad5)") (class "Default")
      (node (ref "U$7") (pin "5") (pinfunction "5.CTS_5") (pintype "bidirectional"))
    )
    (net (code "78") (name "unconnected-(U$8-7.BLK-Pad7)") (class "Default")
      (node (ref "U$8") (pin "7") (pinfunction "7.BLK_7") (pintype "bidirectional"))
    )
    (net (code "79") (name "unconnected-(U$9-11.NC-Pad11)") (class "Default")
      (node (ref "U$9") (pin "11") (pinfunction "11.NC_11") (pintype "bidirectional"))
    )
    (net (code "80") (name "unconnected-(U$9-14.NC-Pad14)") (class "Default")
      (node (ref "U$9") (pin "14") (pinfunction "14.NC_14") (pintype "bidirectional"))
    )
    (net (code "81") (name "unconnected-(U$9-19.INTB-Pad19)") (class "Default")
      (node (ref "U$9") (pin "19") (pinfunction "19.INTB_19") (pintype "bidirectional"))
    )
    (net (code "82") (name "unconnected-(U$9-20.INTA-Pad20)") (class "Default")
      (node (ref "U$9") (pin "20") (pinfunction "20.INTA_20") (pintype "bidirectional"))
    )
    (net (code "83") (name "unconnected-(U$11-7.MODE-Pad7)") (class "Default")
      (node (ref "U$11") (pin "7") (pinfunction "7.MODE_7") (pintype "bidirectional"))
    )
  )
)
